# usteps_v4.net
KiCad netlist of a schematic drawn in EAGLE
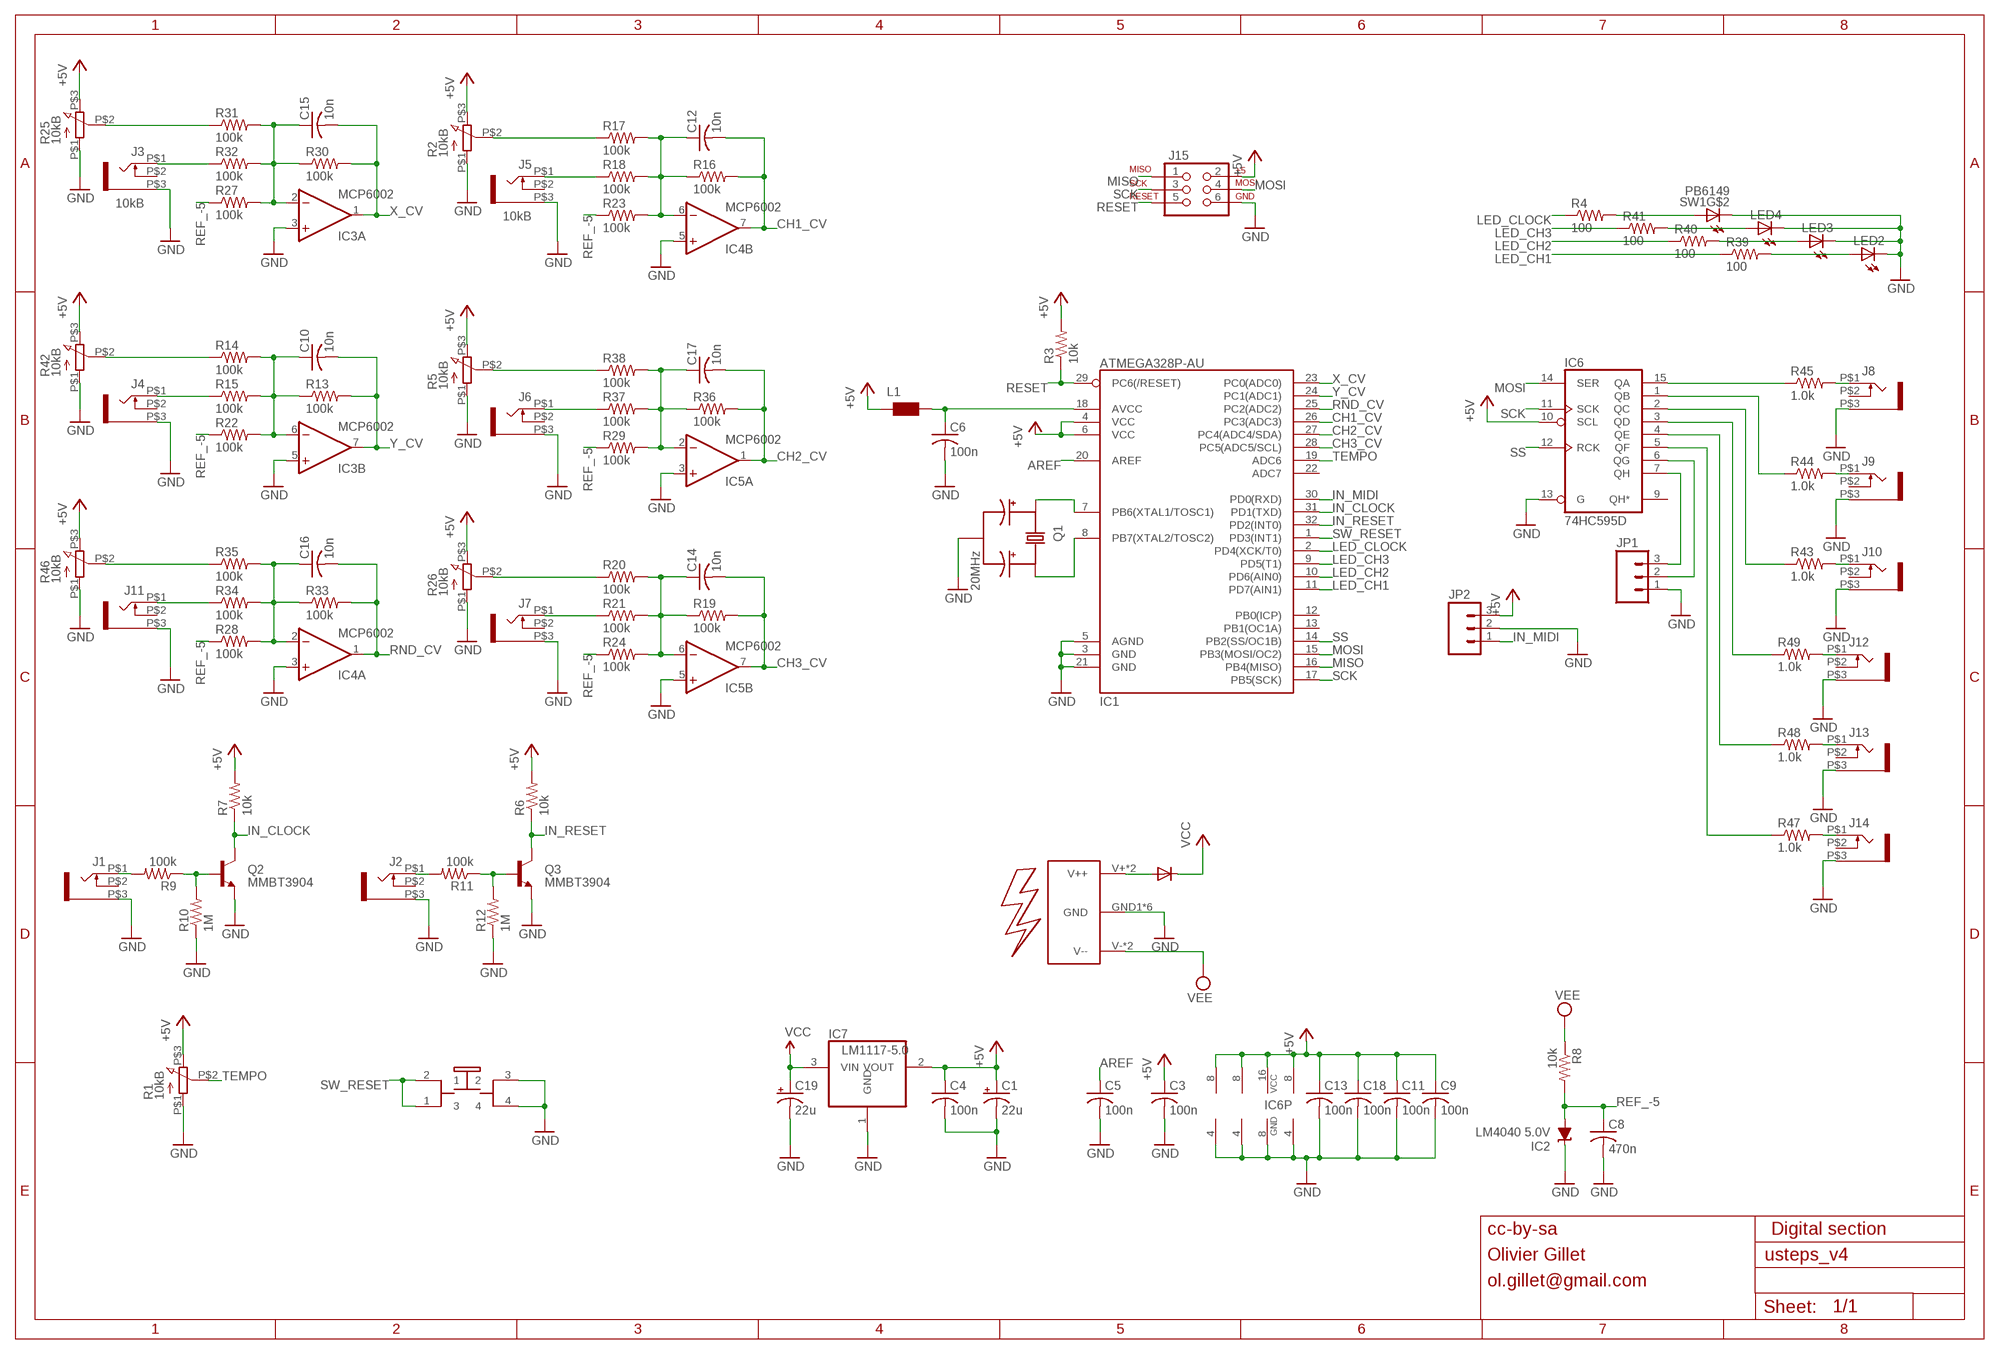
[diagram p0: schematic, sheet 1]

(export (version "E")
  (design (tool "Eeschema 10.0.6"))
  (components
    (comp (ref "C1")
      (value "22u")
      (footprint "eagle-import:PANASONIC_C")
      (libsource (lib "eagle-import") (part "CPOL-USC"))
    )
    (comp (ref "C3")
      (value "100n")
      (footprint "eagle-import:C0603")
      (libsource (lib "eagle-import") (part "C-USC0603"))
    )
    (comp (ref "C4")
      (value "100n")
      (footprint "eagle-import:C0603")
      (libsource (lib "eagle-import") (part "C-USC0603"))
    )
    (comp (ref "C5")
      (value "100n")
      (footprint "eagle-import:C0603")
      (libsource (lib "eagle-import") (part "C-USC0603"))
    )
    (comp (ref "C6")
      (value "100n")
      (footprint "eagle-import:C0603")
      (libsource (lib "eagle-import") (part "C-USC0603"))
    )
    (comp (ref "C8")
      (value "470n")
      (footprint "eagle-import:C0603")
      (libsource (lib "eagle-import") (part "C-USC0603"))
    )
    (comp (ref "C9")
      (value "100n")
      (footprint "eagle-import:C0603")
      (libsource (lib "eagle-import") (part "C-USC0603"))
    )
    (comp (ref "C10")
      (value "10n")
      (footprint "eagle-import:C0603")
      (libsource (lib "eagle-import") (part "C-USC0603"))
    )
    (comp (ref "C11")
      (value "100n")
      (footprint "eagle-import:C0603")
      (libsource (lib "eagle-import") (part "C-USC0603"))
    )
    (comp (ref "C12")
      (value "10n")
      (footprint "eagle-import:C0603")
      (libsource (lib "eagle-import") (part "C-USC0603"))
    )
    (comp (ref "C13")
      (value "100n")
      (footprint "eagle-import:C0603")
      (libsource (lib "eagle-import") (part "C-USC0603"))
    )
    (comp (ref "C14")
      (value "10n")
      (footprint "eagle-import:C0603")
      (libsource (lib "eagle-import") (part "C-USC0603"))
    )
    (comp (ref "C15")
      (value "10n")
      (footprint "eagle-import:C0603")
      (libsource (lib "eagle-import") (part "C-USC0603"))
    )
    (comp (ref "C16")
      (value "10n")
      (footprint "eagle-import:C0603")
      (libsource (lib "eagle-import") (part "C-USC0603"))
    )
    (comp (ref "C17")
      (value "10n")
      (footprint "eagle-import:C0603")
      (libsource (lib "eagle-import") (part "C-USC0603"))
    )
    (comp (ref "C18")
      (value "100n")
      (footprint "eagle-import:C0603")
      (libsource (lib "eagle-import") (part "C-USC0603"))
    )
    (comp (ref "C19")
      (value "22u")
      (footprint "eagle-import:PANASONIC_C")
      (libsource (lib "eagle-import") (part "CPOL-USC"))
    )
    (comp (ref "D2")
      (value "1N5819HW")
      (footprint "eagle-import:SOD123")
      (libsource (lib "eagle-import") (part "DIODE-SOD123"))
    )
    (comp (ref "IC1")
      (value "ATMEGA328P-AU")
      (footprint "eagle-import:TQFP32-08")
      (libsource (lib "eagle-import") (part "ATMEGA168"))
    )
    (comp (ref "IC2")
      (value "LM4040 5.0V")
      (footprint "eagle-import:DBZ_R-PDSO-G3")
      (libsource (lib "eagle-import") (part "LM4041DBZC12"))
    )
    (comp (ref "IC3")
      (value "MCP6002")
      (footprint "eagle-import:SO08")
      (libsource (lib "eagle-import") (part "TL072D"))
    )
    (comp (ref "IC4")
      (value "MCP6002")
      (footprint "eagle-import:SO08")
      (libsource (lib "eagle-import") (part "TL072D"))
    )
    (comp (ref "IC5")
      (value "MCP6002")
      (footprint "eagle-import:SO08")
      (libsource (lib "eagle-import") (part "TL072D"))
    )
    (comp (ref "IC6")
      (value "74HC595D")
      (footprint "eagle-import:SO16")
      (libsource (lib "eagle-import") (part "74595DHC"))
    )
    (comp (ref "IC7")
      (value "LM1117-5.0")
      (footprint "eagle-import:SOT223")
      (libsource (lib "eagle-import") (part "REG1117"))
    )
    (comp (ref "J1")
      (value "WQP-PJ301M-12_JACK")
      (footprint "eagle-import:WQP-PJ301M-12_JACK")
      (libsource (lib "eagle-import") (part "WQP-PJ301M-12_JACK"))
    )
    (comp (ref "J2")
      (value "WQP-PJ301M-12_JACK")
      (footprint "eagle-import:WQP-PJ301M-12_JACK")
      (libsource (lib "eagle-import") (part "WQP-PJ301M-12_JACK"))
    )
    (comp (ref "J3")
      (value "10kB")
      (footprint "eagle-import:WQP-PJ301M-12_JACK")
      (libsource (lib "eagle-import") (part "WQP-PJ301M-12_JACK"))
    )
    (comp (ref "J4")
      (value "WQP-PJ301M-12_JACK")
      (footprint "eagle-import:WQP-PJ301M-12_JACK")
      (libsource (lib "eagle-import") (part "WQP-PJ301M-12_JACK"))
    )
    (comp (ref "J5")
      (value "10kB")
      (footprint "eagle-import:WQP-PJ301M-12_JACK")
      (libsource (lib "eagle-import") (part "WQP-PJ301M-12_JACK"))
    )
    (comp (ref "J6")
      (value "WQP-PJ301M-12_JACK")
      (footprint "eagle-import:WQP-PJ301M-12_JACK")
      (libsource (lib "eagle-import") (part "WQP-PJ301M-12_JACK"))
    )
    (comp (ref "J7")
      (value "WQP-PJ301M-12_JACK")
      (footprint "eagle-import:WQP-PJ301M-12_JACK")
      (libsource (lib "eagle-import") (part "WQP-PJ301M-12_JACK"))
    )
    (comp (ref "J8")
      (value "WQP-PJ301M-12_JACK")
      (footprint "eagle-import:WQP-PJ301M-12_JACK")
      (libsource (lib "eagle-import") (part "WQP-PJ301M-12_JACK"))
    )
    (comp (ref "J9")
      (value "WQP-PJ301M-12_JACK")
      (footprint "eagle-import:WQP-PJ301M-12_JACK")
      (libsource (lib "eagle-import") (part "WQP-PJ301M-12_JACK"))
    )
    (comp (ref "J10")
      (value "WQP-PJ301M-12_JACK")
      (footprint "eagle-import:WQP-PJ301M-12_JACK")
      (libsource (lib "eagle-import") (part "WQP-PJ301M-12_JACK"))
    )
    (comp (ref "J11")
      (value "WQP-PJ301M-12_JACK")
      (footprint "eagle-import:WQP-PJ301M-12_JACK")
      (libsource (lib "eagle-import") (part "WQP-PJ301M-12_JACK"))
    )
    (comp (ref "J12")
      (value "WQP-PJ301M-12_JACK")
      (footprint "eagle-import:WQP-PJ301M-12_JACK")
      (libsource (lib "eagle-import") (part "WQP-PJ301M-12_JACK"))
    )
    (comp (ref "J13")
      (value "WQP-PJ301M-12_JACK")
      (footprint "eagle-import:WQP-PJ301M-12_JACK")
      (libsource (lib "eagle-import") (part "WQP-PJ301M-12_JACK"))
    )
    (comp (ref "J14")
      (value "WQP-PJ301M-12_JACK")
      (footprint "eagle-import:WQP-PJ301M-12_JACK")
      (libsource (lib "eagle-import") (part "WQP-PJ301M-12_JACK"))
    )
    (comp (ref "J15")
      (value "AVR_SPI_PRG_6PTH")
      (footprint "eagle-import:2X3")
      (libsource (lib "eagle-import") (part "AVR_SPI_PRG_6PTH"))
    )
    (comp (ref "JP1")
      (value "M03PTH")
      (footprint "eagle-import:1X03")
      (libsource (lib "eagle-import") (part "M03PTH"))
    )
    (comp (ref "JP2")
      (value "M03PTH")
      (footprint "eagle-import:1X03")
      (libsource (lib "eagle-import") (part "M03PTH"))
    )
    (comp (ref "L1")
      (value "WE-CBF_0603")
      (footprint "eagle-import:0603")
      (libsource (lib "eagle-import") (part "WE-CBF_0603"))
    )
    (comp (ref "LED2")
      (value "LED3MM")
      (footprint "eagle-import:LED3MM")
      (libsource (lib "eagle-import") (part "LED3MM"))
    )
    (comp (ref "LED3")
      (value "LED3MM")
      (footprint "eagle-import:LED3MM")
      (libsource (lib "eagle-import") (part "LED3MM"))
    )
    (comp (ref "LED4")
      (value "LED3MM")
      (footprint "eagle-import:LED3MM")
      (libsource (lib "eagle-import") (part "LED3MM"))
    )
    (comp (ref "Q1")
      (value "20MHz")
      (footprint "eagle-import:INSTRUO_CRYSTAL_SMALLER")
      (libsource (lib "eagle-import") (part "INSTRUO_CRYSTAL_SMALLER"))
    )
    (comp (ref "Q2")
      (value "MMBT3904")
      (footprint "eagle-import:SOT23-BEC")
      (libsource (lib "eagle-import") (part "-NPN-SOT23-BECMMBT3904LT1"))
    )
    (comp (ref "Q3")
      (value "MMBT3904")
      (footprint "eagle-import:SOT23-BEC")
      (libsource (lib "eagle-import") (part "-NPN-SOT23-BECMMBT3904LT1"))
    )
    (comp (ref "R1")
      (value "10kB")
      (footprint "eagle-import:INSTRUO_Q-POT2")
      (libsource (lib "eagle-import") (part "INSTRUO_Q-POT2"))
    )
    (comp (ref "R2")
      (value "10kB")
      (footprint "eagle-import:INSTRUO_Q-POT2")
      (libsource (lib "eagle-import") (part "INSTRUO_Q-POT2"))
    )
    (comp (ref "R3")
      (value "10k")
      (footprint "eagle-import:R0603")
      (libsource (lib "eagle-import") (part "R-US_R0603"))
    )
    (comp (ref "R4")
      (value "100")
      (footprint "eagle-import:R0603")
      (libsource (lib "eagle-import") (part "R-US_R0603"))
    )
    (comp (ref "R5")
      (value "10kB")
      (footprint "eagle-import:INSTRUO_Q-POT2")
      (libsource (lib "eagle-import") (part "INSTRUO_Q-POT2"))
    )
    (comp (ref "R6")
      (value "10k")
      (footprint "eagle-import:R0603")
      (libsource (lib "eagle-import") (part "R-US_R0603"))
    )
    (comp (ref "R7")
      (value "10k")
      (footprint "eagle-import:R0603")
      (libsource (lib "eagle-import") (part "R-US_R0603"))
    )
    (comp (ref "R8")
      (value "10k")
      (footprint "eagle-import:R0603")
      (libsource (lib "eagle-import") (part "resistor_R-US_R0603"))
    )
    (comp (ref "R9")
      (value "100k")
      (footprint "eagle-import:R0603")
      (libsource (lib "eagle-import") (part "R-US_R0603"))
    )
    (comp (ref "R10")
      (value "1M")
      (footprint "eagle-import:R0603")
      (libsource (lib "eagle-import") (part "R-US_R0603"))
    )
    (comp (ref "R11")
      (value "100k")
      (footprint "eagle-import:R0603")
      (libsource (lib "eagle-import") (part "R-US_R0603"))
    )
    (comp (ref "R12")
      (value "1M")
      (footprint "eagle-import:R0603")
      (libsource (lib "eagle-import") (part "R-US_R0603"))
    )
    (comp (ref "R13")
      (value "100k")
      (footprint "eagle-import:R0603")
      (libsource (lib "eagle-import") (part "R-US_R0603"))
    )
    (comp (ref "R14")
      (value "100k")
      (footprint "eagle-import:R0603")
      (libsource (lib "eagle-import") (part "R-US_R0603"))
    )
    (comp (ref "R15")
      (value "100k")
      (footprint "eagle-import:R0603")
      (libsource (lib "eagle-import") (part "R-US_R0603"))
    )
    (comp (ref "R16")
      (value "100k")
      (footprint "eagle-import:R0603")
      (libsource (lib "eagle-import") (part "R-US_R0603"))
    )
    (comp (ref "R17")
      (value "100k")
      (footprint "eagle-import:R0603")
      (libsource (lib "eagle-import") (part "R-US_R0603"))
    )
    (comp (ref "R18")
      (value "100k")
      (footprint "eagle-import:R0603")
      (libsource (lib "eagle-import") (part "R-US_R0603"))
    )
    (comp (ref "R19")
      (value "100k")
      (footprint "eagle-import:R0603")
      (libsource (lib "eagle-import") (part "R-US_R0603"))
    )
    (comp (ref "R20")
      (value "100k")
      (footprint "eagle-import:R0603")
      (libsource (lib "eagle-import") (part "R-US_R0603"))
    )
    (comp (ref "R21")
      (value "100k")
      (footprint "eagle-import:R0603")
      (libsource (lib "eagle-import") (part "R-US_R0603"))
    )
    (comp (ref "R22")
      (value "100k")
      (footprint "eagle-import:R0603")
      (libsource (lib "eagle-import") (part "R-US_R0603"))
    )
    (comp (ref "R23")
      (value "100k")
      (footprint "eagle-import:R0603")
      (libsource (lib "eagle-import") (part "R-US_R0603"))
    )
    (comp (ref "R24")
      (value "100k")
      (footprint "eagle-import:R0603")
      (libsource (lib "eagle-import") (part "R-US_R0603"))
    )
    (comp (ref "R25")
      (value "10kB")
      (footprint "eagle-import:INSTRUO_Q-POT2")
      (libsource (lib "eagle-import") (part "INSTRUO_Q-POT2"))
    )
    (comp (ref "R26")
      (value "10kB")
      (footprint "eagle-import:INSTRUO_Q-POT2")
      (libsource (lib "eagle-import") (part "INSTRUO_Q-POT2"))
    )
    (comp (ref "R27")
      (value "100k")
      (footprint "eagle-import:R0603")
      (libsource (lib "eagle-import") (part "R-US_R0603"))
    )
    (comp (ref "R28")
      (value "100k")
      (footprint "eagle-import:R0603")
      (libsource (lib "eagle-import") (part "R-US_R0603"))
    )
    (comp (ref "R29")
      (value "100k")
      (footprint "eagle-import:R0603")
      (libsource (lib "eagle-import") (part "R-US_R0603"))
    )
    (comp (ref "R30")
      (value "100k")
      (footprint "eagle-import:R0603")
      (libsource (lib "eagle-import") (part "R-US_R0603"))
    )
    (comp (ref "R31")
      (value "100k")
      (footprint "eagle-import:R0603")
      (libsource (lib "eagle-import") (part "R-US_R0603"))
    )
    (comp (ref "R32")
      (value "100k")
      (footprint "eagle-import:R0603")
      (libsource (lib "eagle-import") (part "R-US_R0603"))
    )
    (comp (ref "R33")
      (value "100k")
      (footprint "eagle-import:R0603")
      (libsource (lib "eagle-import") (part "R-US_R0603"))
    )
    (comp (ref "R34")
      (value "100k")
      (footprint "eagle-import:R0603")
      (libsource (lib "eagle-import") (part "R-US_R0603"))
    )
    (comp (ref "R35")
      (value "100k")
      (footprint "eagle-import:R0603")
      (libsource (lib "eagle-import") (part "R-US_R0603"))
    )
    (comp (ref "R36")
      (value "100k")
      (footprint "eagle-import:R0603")
      (libsource (lib "eagle-import") (part "R-US_R0603"))
    )
    (comp (ref "R37")
      (value "100k")
      (footprint "eagle-import:R0603")
      (libsource (lib "eagle-import") (part "R-US_R0603"))
    )
    (comp (ref "R38")
      (value "100k")
      (footprint "eagle-import:R0603")
      (libsource (lib "eagle-import") (part "R-US_R0603"))
    )
    (comp (ref "R39")
      (value "100")
      (footprint "eagle-import:R0603")
      (libsource (lib "eagle-import") (part "R-US_R0603"))
    )
    (comp (ref "R40")
      (value "100")
      (footprint "eagle-import:R0603")
      (libsource (lib "eagle-import") (part "R-US_R0603"))
    )
    (comp (ref "R41")
      (value "100")
      (footprint "eagle-import:R0603")
      (libsource (lib "eagle-import") (part "R-US_R0603"))
    )
    (comp (ref "R42")
      (value "10kB")
      (footprint "eagle-import:INSTRUO_Q-POT2")
      (libsource (lib "eagle-import") (part "INSTRUO_Q-POT2"))
    )
    (comp (ref "R43")
      (value "1.0k")
      (footprint "eagle-import:R0603")
      (libsource (lib "eagle-import") (part "R-US_R0603"))
    )
    (comp (ref "R44")
      (value "1.0k")
      (footprint "eagle-import:R0603")
      (libsource (lib "eagle-import") (part "R-US_R0603"))
    )
    (comp (ref "R45")
      (value "1.0k")
      (footprint "eagle-import:R0603")
      (libsource (lib "eagle-import") (part "R-US_R0603"))
    )
    (comp (ref "R46")
      (value "10kB")
      (footprint "eagle-import:INSTRUO_Q-POT2")
      (libsource (lib "eagle-import") (part "INSTRUO_Q-POT2"))
    )
    (comp (ref "R47")
      (value "1.0k")
      (footprint "eagle-import:R0603")
      (libsource (lib "eagle-import") (part "R-US_R0603"))
    )
    (comp (ref "R48")
      (value "1.0k")
      (footprint "eagle-import:R0603")
      (libsource (lib "eagle-import") (part "R-US_R0603"))
    )
    (comp (ref "R49")
      (value "1.0k")
      (footprint "eagle-import:R0603")
      (libsource (lib "eagle-import") (part "R-US_R0603"))
    )
    (comp (ref "SW1")
      (value "PB6149")
      (footprint "eagle-import:INSTRUO_PB6149L")
      (libsource (lib "eagle-import") (part "INSTRUO_PB6149_FIXED"))
    )
    (comp (ref "U$1")
      (value "INSTRUO_EURO_POWER2")
      (footprint "eagle-import:INSTRUO_EURO_POWER2")
      (libsource (lib "eagle-import") (part "INSTRUO_EURO_POWER2"))
    )
  )
  (nets
    (net (code "1") (name "+5V") (class "Default")
      (node (ref "C1") (pin "+") (pinfunction "+_+") (pintype "passive"))
      (node (ref "C11") (pin "1") (pinfunction "1_1") (pintype "passive"))
      (node (ref "C13") (pin "1") (pinfunction "1_1") (pintype "passive"))
      (node (ref "C18") (pin "1") (pinfunction "1_1") (pintype "passive"))
      (node (ref "C3") (pin "1") (pinfunction "1_1") (pintype "passive"))
      (node (ref "C4") (pin "1") (pinfunction "1_1") (pintype "passive"))
      (node (ref "C9") (pin "1") (pinfunction "1_1") (pintype "passive"))
      (node (ref "IC1") (pin "4") (pinfunction "VCC_4") (pintype "bidirectional"))
      (node (ref "IC1") (pin "6") (pinfunction "VCC_6") (pintype "bidirectional"))
      (node (ref "IC3") (pin "8") (pinfunction "V+_8") (pintype "power_in"))
      (node (ref "IC4") (pin "8") (pinfunction "V+_8") (pintype "power_in"))
      (node (ref "IC5") (pin "8") (pinfunction "V+_8") (pintype "power_in"))
      (node (ref "IC6") (pin "10") (pinfunction "SCL_10") (pintype "input"))
      (node (ref "IC6") (pin "16") (pinfunction "VCC_16") (pintype "power_in"))
      (node (ref "IC7") (pin "2") (pinfunction "VOUT_2") (pintype "output"))
      (node (ref "J15") (pin "2") (pinfunction "2_2") (pintype "passive"))
      (node (ref "JP2") (pin "3") (pinfunction "3_3") (pintype "passive"))
      (node (ref "L1") (pin "1") (pinfunction "1_1") (pintype "passive"))
      (node (ref "R1") (pin "P$3") (pinfunction "3_P$3") (pintype "passive"))
      (node (ref "R2") (pin "P$3") (pinfunction "3_P$3") (pintype "passive"))
      (node (ref "R25") (pin "P$3") (pinfunction "3_P$3") (pintype "passive"))
      (node (ref "R26") (pin "P$3") (pinfunction "3_P$3") (pintype "passive"))
      (node (ref "R3") (pin "2") (pinfunction "2_2") (pintype "passive"))
      (node (ref "R42") (pin "P$3") (pinfunction "3_P$3") (pintype "passive"))
      (node (ref "R46") (pin "P$3") (pinfunction "3_P$3") (pintype "passive"))
      (node (ref "R5") (pin "P$3") (pinfunction "3_P$3") (pintype "passive"))
      (node (ref "R6") (pin "2") (pinfunction "2_2") (pintype "passive"))
      (node (ref "R7") (pin "2") (pinfunction "2_2") (pintype "passive"))
    )
    (net (code "2") (name "/AREF") (class "Default")
      (node (ref "C5") (pin "1") (pinfunction "1_1") (pintype "passive"))
      (node (ref "IC1") (pin "20") (pinfunction "AREF_20") (pintype "bidirectional"))
    )
    (net (code "3") (name "/CH1_CV") (class "Default")
      (node (ref "C12") (pin "2") (pinfunction "2_2") (pintype "passive"))
      (node (ref "IC1") (pin "26") (pinfunction "PC3(ADC3)_26") (pintype "bidirectional"))
      (node (ref "IC4") (pin "7") (pinfunction "OUT_7") (pintype "output"))
      (node (ref "R16") (pin "2") (pinfunction "2_2") (pintype "passive"))
    )
    (net (code "4") (name "/CH2_CV") (class "Default")
      (node (ref "C17") (pin "2") (pinfunction "2_2") (pintype "passive"))
      (node (ref "IC1") (pin "27") (pinfunction "PC4(ADC4/SDA)_27") (pintype "bidirectional"))
      (node (ref "IC5") (pin "1") (pinfunction "OUT_1") (pintype "output"))
      (node (ref "R36") (pin "2") (pinfunction "2_2") (pintype "passive"))
    )
    (net (code "5") (name "/CH3_CV") (class "Default")
      (node (ref "C14") (pin "2") (pinfunction "2_2") (pintype "passive"))
      (node (ref "IC1") (pin "28") (pinfunction "PC5(ADC5/SCL)_28") (pintype "bidirectional"))
      (node (ref "IC5") (pin "7") (pinfunction "OUT_7") (pintype "output"))
      (node (ref "R19") (pin "2") (pinfunction "2_2") (pintype "passive"))
    )
    (net (code "6") (name "/IN_CLOCK") (class "Default")
      (node (ref "IC1") (pin "31") (pinfunction "PD1(TXD)_31") (pintype "bidirectional"))
      (node (ref "Q2") (pin "C") (pinfunction "C_C") (pintype "passive"))
      (node (ref "R7") (pin "1") (pinfunction "1_1") (pintype "passive"))
    )
    (net (code "7") (name "/IN_MIDI") (class "Default")
      (node (ref "IC1") (pin "30") (pinfunction "PD0(RXD)_30") (pintype "bidirectional"))
      (node (ref "JP2") (pin "1") (pinfunction "1_1") (pintype "passive"))
    )
    (net (code "8") (name "/IN_RESET") (class "Default")
      (node (ref "IC1") (pin "32") (pinfunction "PD2(INT0)_32") (pintype "bidirectional"))
      (node (ref "Q3") (pin "C") (pinfunction "C_C") (pintype "passive"))
      (node (ref "R6") (pin "1") (pinfunction "1_1") (pintype "passive"))
    )
    (net (code "9") (name "/LED_CH1") (class "Default")
      (node (ref "IC1") (pin "11") (pinfunction "PD7(AIN1)_11") (pintype "bidirectional"))
      (node (ref "R39") (pin "1") (pinfunction "1_1") (pintype "passive"))
    )
    (net (code "10") (name "/LED_CH2") (class "Default")
      (node (ref "IC1") (pin "10") (pinfunction "PD6(AIN0)_10") (pintype "bidirectional"))
      (node (ref "R40") (pin "1") (pinfunction "1_1") (pintype "passive"))
    )
    (net (code "11") (name "/LED_CH3") (class "Default")
      (node (ref "IC1") (pin "9") (pinfunction "PD5(T1)_9") (pintype "bidirectional"))
      (node (ref "R41") (pin "1") (pinfunction "1_1") (pintype "passive"))
    )
    (net (code "12") (name "/LED_CLOCK") (class "Default")
      (node (ref "IC1") (pin "2") (pinfunction "PD4(XCK/T0)_2") (pintype "bidirectional"))
      (node (ref "R4") (pin "1") (pinfunction "1_1") (pintype "passive"))
    )
    (net (code "13") (name "/MISO") (class "Default")
      (node (ref "IC1") (pin "16") (pinfunction "PB4(MISO)_16") (pintype "bidirectional"))
      (node (ref "J15") (pin "1") (pinfunction "1_1") (pintype "passive"))
    )
    (net (code "14") (name "/MOSI") (class "Default")
      (node (ref "IC1") (pin "15") (pinfunction "PB3(MOSI/OC2)_15") (pintype "bidirectional"))
      (node (ref "IC6") (pin "14") (pinfunction "SER_14") (pintype "input"))
      (node (ref "J15") (pin "4") (pinfunction "4_4") (pintype "passive"))
    )
    (net (code "15") (name "/REF_-5") (class "Default")
      (node (ref "C8") (pin "1") (pinfunction "1_1") (pintype "passive"))
      (node (ref "IC2") (pin "2") (pinfunction "A_2") (pintype "passive"))
      (node (ref "R22") (pin "1") (pinfunction "1_1") (pintype "passive"))
      (node (ref "R23") (pin "1") (pinfunction "1_1") (pintype "passive"))
      (node (ref "R24") (pin "1") (pinfunction "1_1") (pintype "passive"))
      (node (ref "R27") (pin "1") (pinfunction "1_1") (pintype "passive"))
      (node (ref "R28") (pin "1") (pinfunction "1_1") (pintype "passive"))
      (node (ref "R29") (pin "1") (pinfunction "1_1") (pintype "passive"))
      (node (ref "R8") (pin "2") (pinfunction "2_2") (pintype "passive"))
    )
    (net (code "16") (name "/RESET") (class "Default")
      (node (ref "IC1") (pin "29") (pinfunction "PC6(/RESET)_29") (pintype "bidirectional"))
      (node (ref "J15") (pin "5") (pinfunction "5_5") (pintype "passive"))
      (node (ref "R3") (pin "1") (pinfunction "1_1") (pintype "passive"))
    )
    (net (code "17") (name "/RND_CV") (class "Default")
      (node (ref "C16") (pin "2") (pinfunction "2_2") (pintype "passive"))
      (node (ref "IC1") (pin "25") (pinfunction "PC2(ADC2)_25") (pintype "bidirectional"))
      (node (ref "IC4") (pin "1") (pinfunction "OUT_1") (pintype "output"))
      (node (ref "R33") (pin "2") (pinfunction "2_2") (pintype "passive"))
    )
    (net (code "18") (name "/SCK") (class "Default")
      (node (ref "IC1") (pin "17") (pinfunction "PB5(SCK)_17") (pintype "bidirectional"))
      (node (ref "IC6") (pin "11") (pinfunction "SCK_11") (pintype "input"))
      (node (ref "J15") (pin "3") (pinfunction "3_3") (pintype "passive"))
    )
    (net (code "19") (name "/SS") (class "Default")
      (node (ref "IC1") (pin "14") (pinfunction "PB2(SS/OC1B)_14") (pintype "bidirectional"))
      (node (ref "IC6") (pin "12") (pinfunction "RCK_12") (pintype "input"))
    )
    (net (code "20") (name "/SW_RESET") (class "Default")
      (node (ref "IC1") (pin "1") (pinfunction "PD3(INT1)_1") (pintype "bidirectional"))
      (node (ref "SW1") (pin "1") (pinfunction "3_1") (pintype "bidirectional"))
      (node (ref "SW1") (pin "2") (pinfunction "1_2") (pintype "bidirectional"))
    )
    (net (code "21") (name "/TEMPO") (class "Default")
      (node (ref "IC1") (pin "19") (pinfunction "ADC6_19") (pintype "bidirectional"))
      (node (ref "R1") (pin "P$2") (pinfunction "2_P$2") (pintype "passive"))
    )
    (net (code "22") (name "/X_CV") (class "Default")
      (node (ref "C15") (pin "2") (pinfunction "2_2") (pintype "passive"))
      (node (ref "IC1") (pin "23") (pinfunction "PC0(ADC0)_23") (pintype "bidirectional"))
      (node (ref "IC3") (pin "1") (pinfunction "OUT_1") (pintype "output"))
      (node (ref "R30") (pin "2") (pinfunction "2_2") (pintype "passive"))
    )
    (net (code "23") (name "/Y_CV") (class "Default")
      (node (ref "C10") (pin "2") (pinfunction "2_2") (pintype "passive"))
      (node (ref "IC1") (pin "24") (pinfunction "PC1(ADC1)_24") (pintype "bidirectional"))
      (node (ref "IC3") (pin "7") (pinfunction "OUT_7") (pintype "output"))
      (node (ref "R13") (pin "2") (pinfunction "2_2") (pintype "passive"))
    )
    (net (code "24") (name "GND") (class "Default")
      (node (ref "C1") (pin "-") (pinfunction "-_-") (pintype "passive"))
      (node (ref "C11") (pin "2") (pinfunction "2_2") (pintype "passive"))
      (node (ref "C13") (pin "2") (pinfunction "2_2") (pintype "passive"))
      (node (ref "C18") (pin "2") (pinfunction "2_2") (pintype "passive"))
      (node (ref "C19") (pin "-") (pinfunction "-_-") (pintype "passive"))
      (node (ref "C3") (pin "2") (pinfunction "2_2") (pintype "passive"))
      (node (ref "C4") (pin "2") (pinfunction "2_2") (pintype "passive"))
      (node (ref "C5") (pin "2") (pinfunction "2_2") (pintype "passive"))
      (node (ref "C6") (pin "2") (pinfunction "2_2") (pintype "passive"))
      (node (ref "C8") (pin "2") (pinfunction "2_2") (pintype "passive"))
      (node (ref "C9") (pin "2") (pinfunction "2_2") (pintype "passive"))
      (node (ref "IC1") (pin "21") (pinfunction "GND_21") (pintype "bidirectional"))
      (node (ref "IC1") (pin "3") (pinfunction "GND_3") (pintype "bidirectional"))
      (node (ref "IC1") (pin "5") (pinfunction "AGND_5") (pintype "bidirectional"))
      (node (ref "IC2") (pin "1") (pinfunction "C_1") (pintype "passive"))
      (node (ref "IC3") (pin "3") (pinfunction "+IN_3") (pintype "input"))
      (node (ref "IC3") (pin "4") (pinfunction "V-_4") (pintype "power_in"))
      (node (ref "IC3") (pin "5") (pinfunction "+IN_5") (pintype "input"))
      (node (ref "IC4") (pin "3") (pinfunction "+IN_3") (pintype "input"))
      (node (ref "IC4") (pin "4") (pinfunction "V-_4") (pintype "power_in"))
      (node (ref "IC4") (pin "5") (pinfunction "+IN_5") (pintype "input"))
      (node (ref "IC5") (pin "3") (pinfunction "+IN_3") (pintype "input"))
      (node (ref "IC5") (pin "4") (pinfunction "V-_4") (pintype "power_in"))
      (node (ref "IC5") (pin "5") (pinfunction "+IN_5") (pintype "input"))
      (node (ref "IC6") (pin "13") (pinfunction "G_13") (pintype "input"))
      (node (ref "IC6") (pin "8") (pinfunction "GND_8") (pintype "power_in"))
      (node (ref "IC7") (pin "1") (pinfunction "GND_1") (pintype "power_in"))
      (node (ref "J1") (pin "P$3") (pinfunction "1_P$3") (pintype "passive"))
      (node (ref "J10") (pin "P$3") (pinfunction "1_P$3") (pintype "passive"))
      (node (ref "J11") (pin "P$3") (pinfunction "1_P$3") (pintype "passive"))
      (node (ref "J12") (pin "P$3") (pinfunction "1_P$3") (pintype "passive"))
      (node (ref "J13") (pin "P$3") (pinfunction "1_P$3") (pintype "passive"))
      (node (ref "J14") (pin "P$3") (pinfunction "1_P$3") (pintype "passive"))
      (node (ref "J15") (pin "6") (pinfunction "6_6") (pintype "passive"))
      (node (ref "J2") (pin "P$3") (pinfunction "1_P$3") (pintype "passive"))
      (node (ref "J3") (pin "P$3") (pinfunction "1_P$3") (pintype "passive"))
      (node (ref "J4") (pin "P$3") (pinfunction "1_P$3") (pintype "passive"))
      (node (ref "J5") (pin "P$3") (pinfunction "1_P$3") (pintype "passive"))
      (node (ref "J6") (pin "P$3") (pinfunction "1_P$3") (pintype "passive"))
      (node (ref "J7") (pin "P$3") (pinfunction "1_P$3") (pintype "passive"))
      (node (ref "J8") (pin "P$3") (pinfunction "1_P$3") (pintype "passive"))
      (node (ref "J9") (pin "P$3") (pinfunction "1_P$3") (pintype "passive"))
      (node (ref "JP1") (pin "1") (pinfunction "1_1") (pintype "passive"))
      (node (ref "JP2") (pin "2") (pinfunction "2_2") (pintype "passive"))
      (node (ref "LED2") (pin "K") (pinfunction "C_K") (pintype "passive"))
      (node (ref "LED3") (pin "K") (pinfunction "C_K") (pintype "passive"))
      (node (ref "LED4") (pin "K") (pinfunction "C_K") (pintype "passive"))
      (node (ref "Q1") (pin "GND") (pinfunction "GND_GND") (pintype "bidirectional"))
      (node (ref "Q2") (pin "E") (pinfunction "E_E") (pintype "passive"))
      (node (ref "Q3") (pin "E") (pinfunction "E_E") (pintype "passive"))
      (node (ref "R1") (pin "P$1") (pinfunction "1_P$1") (pintype "passive"))
      (node (ref "R10") (pin "1") (pinfunction "1_1") (pintype "passive"))
      (node (ref "R12") (pin "1") (pinfunction "1_1") (pintype "passive"))
      (node (ref "R2") (pin "P$1") (pinfunction "1_P$1") (pintype "passive"))
      (node (ref "R25") (pin "P$1") (pinfunction "1_P$1") (pintype "passive"))
      (node (ref "R26") (pin "P$1") (pinfunction "1_P$1") (pintype "passive"))
      (node (ref "R42") (pin "P$1") (pinfunction "1_P$1") (pintype "passive"))
      (node (ref "R46") (pin "P$1") (pinfunction "1_P$1") (pintype "passive"))
      (node (ref "R5") (pin "P$1") (pinfunction "1_P$1") (pintype "passive"))
      (node (ref "SW1") (pin "3") (pinfunction "2_3") (pintype "bidirectional"))
      (node (ref "SW1") (pin "4") (pinfunction "4_4") (pintype "bidirectional"))
      (node (ref "SW1") (pin "K") (pinfunction "C_K") (pintype "passive"))
      (node (ref "U$1") (pin "GND1") (pinfunction "GND_GND1") (pintype "bidirectional"))
      (node (ref "U$1") (pin "GND2") (pinfunction "GND_GND2") (pintype "bidirectional"))
      (node (ref "U$1") (pin "GND3") (pinfunction "GND_GND3") (pintype "bidirectional"))
      (node (ref "U$1") (pin "GND4") (pinfunction "GND_GND4") (pintype "bidirectional"))
      (node (ref "U$1") (pin "GND5") (pinfunction "GND_GND5") (pintype "bidirectional"))
      (node (ref "U$1") (pin "GND6") (pinfunction "GND_GND6") (pintype "bidirectional"))
    )
    (net (code "25") (name "Net-(D2-PadA)") (class "Default")
      (node (ref "D2") (pin "A") (pinfunction "A_A") (pintype "passive"))
      (node (ref "U$1") (pin "V+") (pinfunction "V++_V+") (pintype "bidirectional"))
      (node (ref "U$1") (pin "V++") (pinfunction "V++_V++") (pintype "bidirectional"))
    )
    (net (code "26") (name "Net-(IC1-AVCC)") (class "Default")
      (node (ref "C6") (pin "1") (pinfunction "1_1") (pintype "passive"))
      (node (ref "IC1") (pin "18") (pinfunction "AVCC_18") (pintype "bidirectional"))
      (node (ref "L1") (pin "2") (pinfunction "2_2") (pintype "passive"))
    )
    (net (code "27") (name "Net-(IC1-PB6(XTAL1{slash}TOSC1))") (class "Default")
      (node (ref "IC1") (pin "7") (pinfunction "PB6(XTAL1/TOSC1)_7") (pintype "bidirectional"))
      (node (ref "Q1") (pin "X1") (pinfunction "X1_X1") (pintype "bidirectional"))
    )
    (net (code "28") (name "Net-(IC1-PB7(XTAL2{slash}TOSC2))") (class "Default")
      (node (ref "IC1") (pin "8") (pinfunction "PB7(XTAL2/TOSC2)_8") (pintype "bidirectional"))
      (node (ref "Q1") (pin "X2") (pinfunction "X2_X2") (pintype "bidirectional"))
    )
    (net (code "29") (name "Net-(IC3A--IN)") (class "Default")
      (node (ref "C15") (pin "1") (pinfunction "1_1") (pintype "passive"))
      (node (ref "IC3") (pin "2") (pinfunction "-IN_2") (pintype "input"))
      (node (ref "R27") (pin "2") (pinfunction "2_2") (pintype "passive"))
      (node (ref "R30") (pin "1") (pinfunction "1_1") (pintype "passive"))
      (node (ref "R31") (pin "2") (pinfunction "2_2") (pintype "passive"))
      (node (ref "R32") (pin "2") (pinfunction "2_2") (pintype "passive"))
    )
    (net (code "30") (name "Net-(IC3B--IN)") (class "Default")
      (node (ref "C10") (pin "1") (pinfunction "1_1") (pintype "passive"))
      (node (ref "IC3") (pin "6") (pinfunction "-IN_6") (pintype "input"))
      (node (ref "R13") (pin "1") (pinfunction "1_1") (pintype "passive"))
      (node (ref "R14") (pin "2") (pinfunction "2_2") (pintype "passive"))
      (node (ref "R15") (pin "2") (pinfunction "2_2") (pintype "passive"))
      (node (ref "R22") (pin "2") (pinfunction "2_2") (pintype "passive"))
    )
    (net (code "31") (name "Net-(IC4A--IN)") (class "Default")
      (node (ref "C16") (pin "1") (pinfunction "1_1") (pintype "passive"))
      (node (ref "IC4") (pin "2") (pinfunction "-IN_2") (pintype "input"))
      (node (ref "R28") (pin "2") (pinfunction "2_2") (pintype "passive"))
      (node (ref "R33") (pin "1") (pinfunction "1_1") (pintype "passive"))
      (node (ref "R34") (pin "2") (pinfunction "2_2") (pintype "passive"))
      (node (ref "R35") (pin "2") (pinfunction "2_2") (pintype "passive"))
    )
    (net (code "32") (name "Net-(IC4B--IN)") (class "Default")
      (node (ref "C12") (pin "1") (pinfunction "1_1") (pintype "passive"))
      (node (ref "IC4") (pin "6") (pinfunction "-IN_6") (pintype "input"))
      (node (ref "R16") (pin "1") (pinfunction "1_1") (pintype "passive"))
      (node (ref "R17") (pin "2") (pinfunction "2_2") (pintype "passive"))
      (node (ref "R18") (pin "2") (pinfunction "2_2") (pintype "passive"))
      (node (ref "R23") (pin "2") (pinfunction "2_2") (pintype "passive"))
    )
    (net (code "33") (name "Net-(IC5A--IN)") (class "Default")
      (node (ref "C17") (pin "1") (pinfunction "1_1") (pintype "passive"))
      (node (ref "IC5") (pin "2") (pinfunction "-IN_2") (pintype "input"))
      (node (ref "R29") (pin "2") (pinfunction "2_2") (pintype "passive"))
      (node (ref "R36") (pin "1") (pinfunction "1_1") (pintype "passive"))
      (node (ref "R37") (pin "2") (pinfunction "2_2") (pintype "passive"))
      (node (ref "R38") (pin "2") (pinfunction "2_2") (pintype "passive"))
    )
    (net (code "34") (name "Net-(IC5B--IN)") (class "Default")
      (node (ref "C14") (pin "1") (pinfunction "1_1") (pintype "passive"))
      (node (ref "IC5") (pin "6") (pinfunction "-IN_6") (pintype "input"))
      (node (ref "R19") (pin "1") (pinfunction "1_1") (pintype "passive"))
      (node (ref "R20") (pin "2") (pinfunction "2_2") (pintype "passive"))
      (node (ref "R21") (pin "2") (pinfunction "2_2") (pintype "passive"))
      (node (ref "R24") (pin "2") (pinfunction "2_2") (pintype "passive"))
    )
    (net (code "35") (name "Net-(IC6A-QA)") (class "Default")
      (node (ref "IC6") (pin "15") (pinfunction "QA_15") (pintype "tri_state"))
      (node (ref "R45") (pin "1") (pinfunction "1_1") (pintype "passive"))
    )
    (net (code "36") (name "Net-(IC6A-QB)") (class "Default")
      (node (ref "IC6") (pin "1") (pinfunction "QB_1") (pintype "tri_state"))
      (node (ref "R44") (pin "1") (pinfunction "1_1") (pintype "passive"))
    )
    (net (code "37") (name "Net-(IC6A-QC)") (class "Default")
      (node (ref "IC6") (pin "2") (pinfunction "QC_2") (pintype "tri_state"))
      (node (ref "R43") (pin "1") (pinfunction "1_1") (pintype "passive"))
    )
    (net (code "38") (name "Net-(IC6A-QD)") (class "Default")
      (node (ref "IC6") (pin "3") (pinfunction "QD_3") (pintype "tri_state"))
      (node (ref "R49") (pin "1") (pinfunction "1_1") (pintype "passive"))
    )
    (net (code "39") (name "Net-(IC6A-QE)") (class "Default")
      (node (ref "IC6") (pin "4") (pinfunction "QE_4") (pintype "tri_state"))
      (node (ref "R48") (pin "1") (pinfunction "1_1") (pintype "passive"))
    )
    (net (code "40") (name "Net-(IC6A-QF)") (class "Default")
      (node (ref "IC6") (pin "5") (pinfunction "QF_5") (pintype "tri_state"))
      (node (ref "R47") (pin "1") (pinfunction "1_1") (pintype "passive"))
    )
    (net (code "41") (name "Net-(IC6A-QG)") (class "Default")
      (node (ref "IC6") (pin "6") (pinfunction "QG_6") (pintype "tri_state"))
      (node (ref "JP1") (pin "2") (pinfunction "2_2") (pintype "passive"))
    )
    (net (code "42") (name "Net-(IC6A-QH)") (class "Default")
      (node (ref "IC6") (pin "7") (pinfunction "QH_7") (pintype "tri_state"))
      (node (ref "JP1") (pin "3") (pinfunction "3_3") (pintype "passive"))
    )
    (net (code "43") (name "Net-(J1-2)") (class "Default")
      (node (ref "J1") (pin "P$1") (pinfunction "2_P$1") (pintype "passive"))
      (node (ref "R9") (pin "2") (pinfunction "2_2") (pintype "passive"))
    )
    (net (code "44") (name "Net-(J2-2)") (class "Default")
      (node (ref "J2") (pin "P$1") (pinfunction "2_P$1") (pintype "passive"))
      (node (ref "R11") (pin "2") (pinfunction "2_2") (pintype "passive"))
    )
    (net (code "45") (name "Net-(J3-2)") (class "Default")
      (node (ref "J3") (pin "P$1") (pinfunction "2_P$1") (pintype "passive"))
      (node (ref "R32") (pin "1") (pinfunction "1_1") (pintype "passive"))
    )
    (net (code "46") (name "Net-(J4-2)") (class "Default")
      (node (ref "J4") (pin "P$1") (pinfunction "2_P$1") (pintype "passive"))
      (node (ref "R15") (pin "1") (pinfunction "1_1") (pintype "passive"))
    )
    (net (code "47") (name "Net-(J5-2)") (class "Default")
      (node (ref "J5") (pin "P$1") (pinfunction "2_P$1") (pintype "passive"))
      (node (ref "R18") (pin "1") (pinfunction "1_1") (pintype "passive"))
    )
    (net (code "48") (name "Net-(J6-2)") (class "Default")
      (node (ref "J6") (pin "P$1") (pinfunction "2_P$1") (pintype "passive"))
      (node (ref "R37") (pin "1") (pinfunction "1_1") (pintype "passive"))
    )
    (net (code "49") (name "Net-(J7-2)") (class "Default")
      (node (ref "J7") (pin "P$1") (pinfunction "2_P$1") (pintype "passive"))
      (node (ref "R21") (pin "1") (pinfunction "1_1") (pintype "passive"))
    )
    (net (code "50") (name "Net-(J8-2)") (class "Default")
      (node (ref "J8") (pin "P$1") (pinfunction "2_P$1") (pintype "passive"))
      (node (ref "R45") (pin "2") (pinfunction "2_2") (pintype "passive"))
    )
    (net (code "51") (name "Net-(J9-2)") (class "Default")
      (node (ref "J9") (pin "P$1") (pinfunction "2_P$1") (pintype "passive"))
      (node (ref "R44") (pin "2") (pinfunction "2_2") (pintype "passive"))
    )
    (net (code "52") (name "Net-(J10-2)") (class "Default")
      (node (ref "J10") (pin "P$1") (pinfunction "2_P$1") (pintype "passive"))
      (node (ref "R43") (pin "2") (pinfunction "2_2") (pintype "passive"))
    )
    (net (code "53") (name "Net-(J11-2)") (class "Default")
      (node (ref "J11") (pin "P$1") (pinfunction "2_P$1") (pintype "passive"))
      (node (ref "R34") (pin "1") (pinfunction "1_1") (pintype "passive"))
    )
    (net (code "54") (name "Net-(J12-2)") (class "Default")
      (node (ref "J12") (pin "P$1") (pinfunction "2_P$1") (pintype "passive"))
      (node (ref "R49") (pin "2") (pinfunction "2_2") (pintype "passive"))
    )
    (net (code "55") (name "Net-(J13-2)") (class "Default")
      (node (ref "J13") (pin "P$1") (pinfunction "2_P$1") (pintype "passive"))
      (node (ref "R48") (pin "2") (pinfunction "2_2") (pintype "passive"))
    )
    (net (code "56") (name "Net-(J14-2)") (class "Default")
      (node (ref "J14") (pin "P$1") (pinfunction "2_P$1") (pintype "passive"))
      (node (ref "R47") (pin "2") (pinfunction "2_2") (pintype "passive"))
    )
    (net (code "57") (name "Net-(LED2-PadA)") (class "Default")
      (node (ref "LED2") (pin "A") (pinfunction "A_A") (pintype "passive"))
      (node (ref "R39") (pin "2") (pinfunction "2_2") (pintype "passive"))
    )
    (net (code "58") (name "Net-(LED3-PadA)") (class "Default")
      (node (ref "LED3") (pin "A") (pinfunction "A_A") (pintype "passive"))
      (node (ref "R40") (pin "2") (pinfunction "2_2") (pintype "passive"))
    )
    (net (code "59") (name "Net-(LED4-PadA)") (class "Default")
      (node (ref "LED4") (pin "A") (pinfunction "A_A") (pintype "passive"))
      (node (ref "R41") (pin "2") (pinfunction "2_2") (pintype "passive"))
    )
    (net (code "60") (name "Net-(Q2-PadB)") (class "Default")
      (node (ref "Q2") (pin "B") (pinfunction "B_B") (pintype "passive"))
      (node (ref "R10") (pin "2") (pinfunction "2_2") (pintype "passive"))
      (node (ref "R9") (pin "1") (pinfunction "1_1") (pintype "passive"))
    )
    (net (code "61") (name "Net-(Q3-PadB)") (class "Default")
      (node (ref "Q3") (pin "B") (pinfunction "B_B") (pintype "passive"))
      (node (ref "R11") (pin "1") (pinfunction "1_1") (pintype "passive"))
      (node (ref "R12") (pin "2") (pinfunction "2_2") (pintype "passive"))
    )
    (net (code "62") (name "Net-(R2-2)") (class "Default")
      (node (ref "R17") (pin "1") (pinfunction "1_1") (pintype "passive"))
      (node (ref "R2") (pin "P$2") (pinfunction "2_P$2") (pintype "passive"))
    )
    (net (code "63") (name "Net-(R4-Pad2)") (class "Default")
      (node (ref "R4") (pin "2") (pinfunction "2_2") (pintype "passive"))
      (node (ref "SW1") (pin "A") (pinfunction "A_A") (pintype "passive"))
    )
    (net (code "64") (name "Net-(R5-2)") (class "Default")
      (node (ref "R38") (pin "1") (pinfunction "1_1") (pintype "passive"))
      (node (ref "R5") (pin "P$2") (pinfunction "2_P$2") (pintype "passive"))
    )
    (net (code "65") (name "Net-(R25-2)") (class "Default")
      (node (ref "R25") (pin "P$2") (pinfunction "2_P$2") (pintype "passive"))
      (node (ref "R31") (pin "1") (pinfunction "1_1") (pintype "passive"))
    )
    (net (code "66") (name "Net-(R26-2)") (class "Default")
      (node (ref "R20") (pin "1") (pinfunction "1_1") (pintype "passive"))
      (node (ref "R26") (pin "P$2") (pinfunction "2_P$2") (pintype "passive"))
    )
    (net (code "67") (name "Net-(R42-2)") (class "Default")
      (node (ref "R14") (pin "1") (pinfunction "1_1") (pintype "passive"))
      (node (ref "R42") (pin "P$2") (pinfunction "2_P$2") (pintype "passive"))
    )
    (net (code "68") (name "Net-(R46-2)") (class "Default")
      (node (ref "R35") (pin "1") (pinfunction "1_1") (pintype "passive"))
      (node (ref "R46") (pin "P$2") (pinfunction "2_P$2") (pintype "passive"))
    )
    (net (code "69") (name "VCC") (class "Default")
      (node (ref "C19") (pin "+") (pinfunction "+_+") (pintype "passive"))
      (node (ref "D2") (pin "C") (pinfunction "C_C") (pintype "passive"))
      (node (ref "IC7") (pin "3") (pinfunction "VIN_3") (pintype "input"))
    )
    (net (code "70") (name "VEE") (class "Default")
      (node (ref "R8") (pin "1") (pinfunction "1_1") (pintype "passive"))
      (node (ref "U$1") (pin "V-") (pinfunction "V--_V-") (pintype "bidirectional"))
      (node (ref "U$1") (pin "V--") (pinfunction "V--_V--") (pintype "bidirectional"))
    )
    (net (code "71") (name "unconnected-(IC1-ADC7-Pad22)") (class "Default")
      (node (ref "IC1") (pin "22") (pinfunction "ADC7_22") (pintype "bidirectional"))
    )
    (net (code "72") (name "unconnected-(IC1-PB0(ICP)-Pad12)") (class "Default")
      (node (ref "IC1") (pin "12") (pinfunction "PB0(ICP)_12") (pintype "bidirectional"))
    )
    (net (code "73") (name "unconnected-(IC1-PB1(OC1A)-Pad13)") (class "Default")
      (node (ref "IC1") (pin "13") (pinfunction "PB1(OC1A)_13") (pintype "bidirectional"))
    )
    (net (code "74") (name "unconnected-(IC6A-QH*-Pad9)") (class "Default")
      (node (ref "IC6") (pin "9") (pinfunction "QH*_9") (pintype "tri_state"))
    )
    (net (code "75") (name "unconnected-(J1-3-PadP$2)") (class "Default")
      (node (ref "J1") (pin "P$2") (pinfunction "3_P$2") (pintype "passive"))
    )
    (net (code "76") (name "unconnected-(J2-3-PadP$2)") (class "Default")
      (node (ref "J2") (pin "P$2") (pinfunction "3_P$2") (pintype "passive"))
    )
    (net (code "77") (name "unconnected-(J3-3-PadP$2)") (class "Default")
      (node (ref "J3") (pin "P$2") (pinfunction "3_P$2") (pintype "passive"))
    )
    (net (code "78") (name "unconnected-(J4-3-PadP$2)") (class "Default")
      (node (ref "J4") (pin "P$2") (pinfunction "3_P$2") (pintype "passive"))
    )
    (net (code "79") (name "unconnected-(J5-3-PadP$2)") (class "Default")
      (node (ref "J5") (pin "P$2") (pinfunction "3_P$2") (pintype "passive"))
    )
    (net (code "80") (name "unconnected-(J6-3-PadP$2)") (class "Default")
      (node (ref "J6") (pin "P$2") (pinfunction "3_P$2") (pintype "passive"))
    )
    (net (code "81") (name "unconnected-(J7-3-PadP$2)") (class "Default")
      (node (ref "J7") (pin "P$2") (pinfunction "3_P$2") (pintype "passive"))
    )
    (net (code "82") (name "unconnected-(J8-3-PadP$2)") (class "Default")
      (node (ref "J8") (pin "P$2") (pinfunction "3_P$2") (pintype "passive"))
    )
    (net (code "83") (name "unconnected-(J9-3-PadP$2)") (class "Default")
      (node (ref "J9") (pin "P$2") (pinfunction "3_P$2") (pintype "passive"))
    )
    (net (code "84") (name "unconnected-(J10-3-PadP$2)") (class "Default")
      (node (ref "J10") (pin "P$2") (pinfunction "3_P$2") (pintype "passive"))
    )
    (net (code "85") (name "unconnected-(J11-3-PadP$2)") (class "Default")
      (node (ref "J11") (pin "P$2") (pinfunction "3_P$2") (pintype "passive"))
    )
    (net (code "86") (name "unconnected-(J12-3-PadP$2)") (class "Default")
      (node (ref "J12") (pin "P$2") (pinfunction "3_P$2") (pintype "passive"))
    )
    (net (code "87") (name "unconnected-(J13-3-PadP$2)") (class "Default")
      (node (ref "J13") (pin "P$2") (pinfunction "3_P$2") (pintype "passive"))
    )
    (net (code "88") (name "unconnected-(J14-3-PadP$2)") (class "Default")
      (node (ref "J14") (pin "P$2") (pinfunction "3_P$2") (pintype "passive"))
    )
  )
)
